# VentilatorRev1InterimDaughtercard.net
KiCad netlist of a schematic drawn in Altium Designer
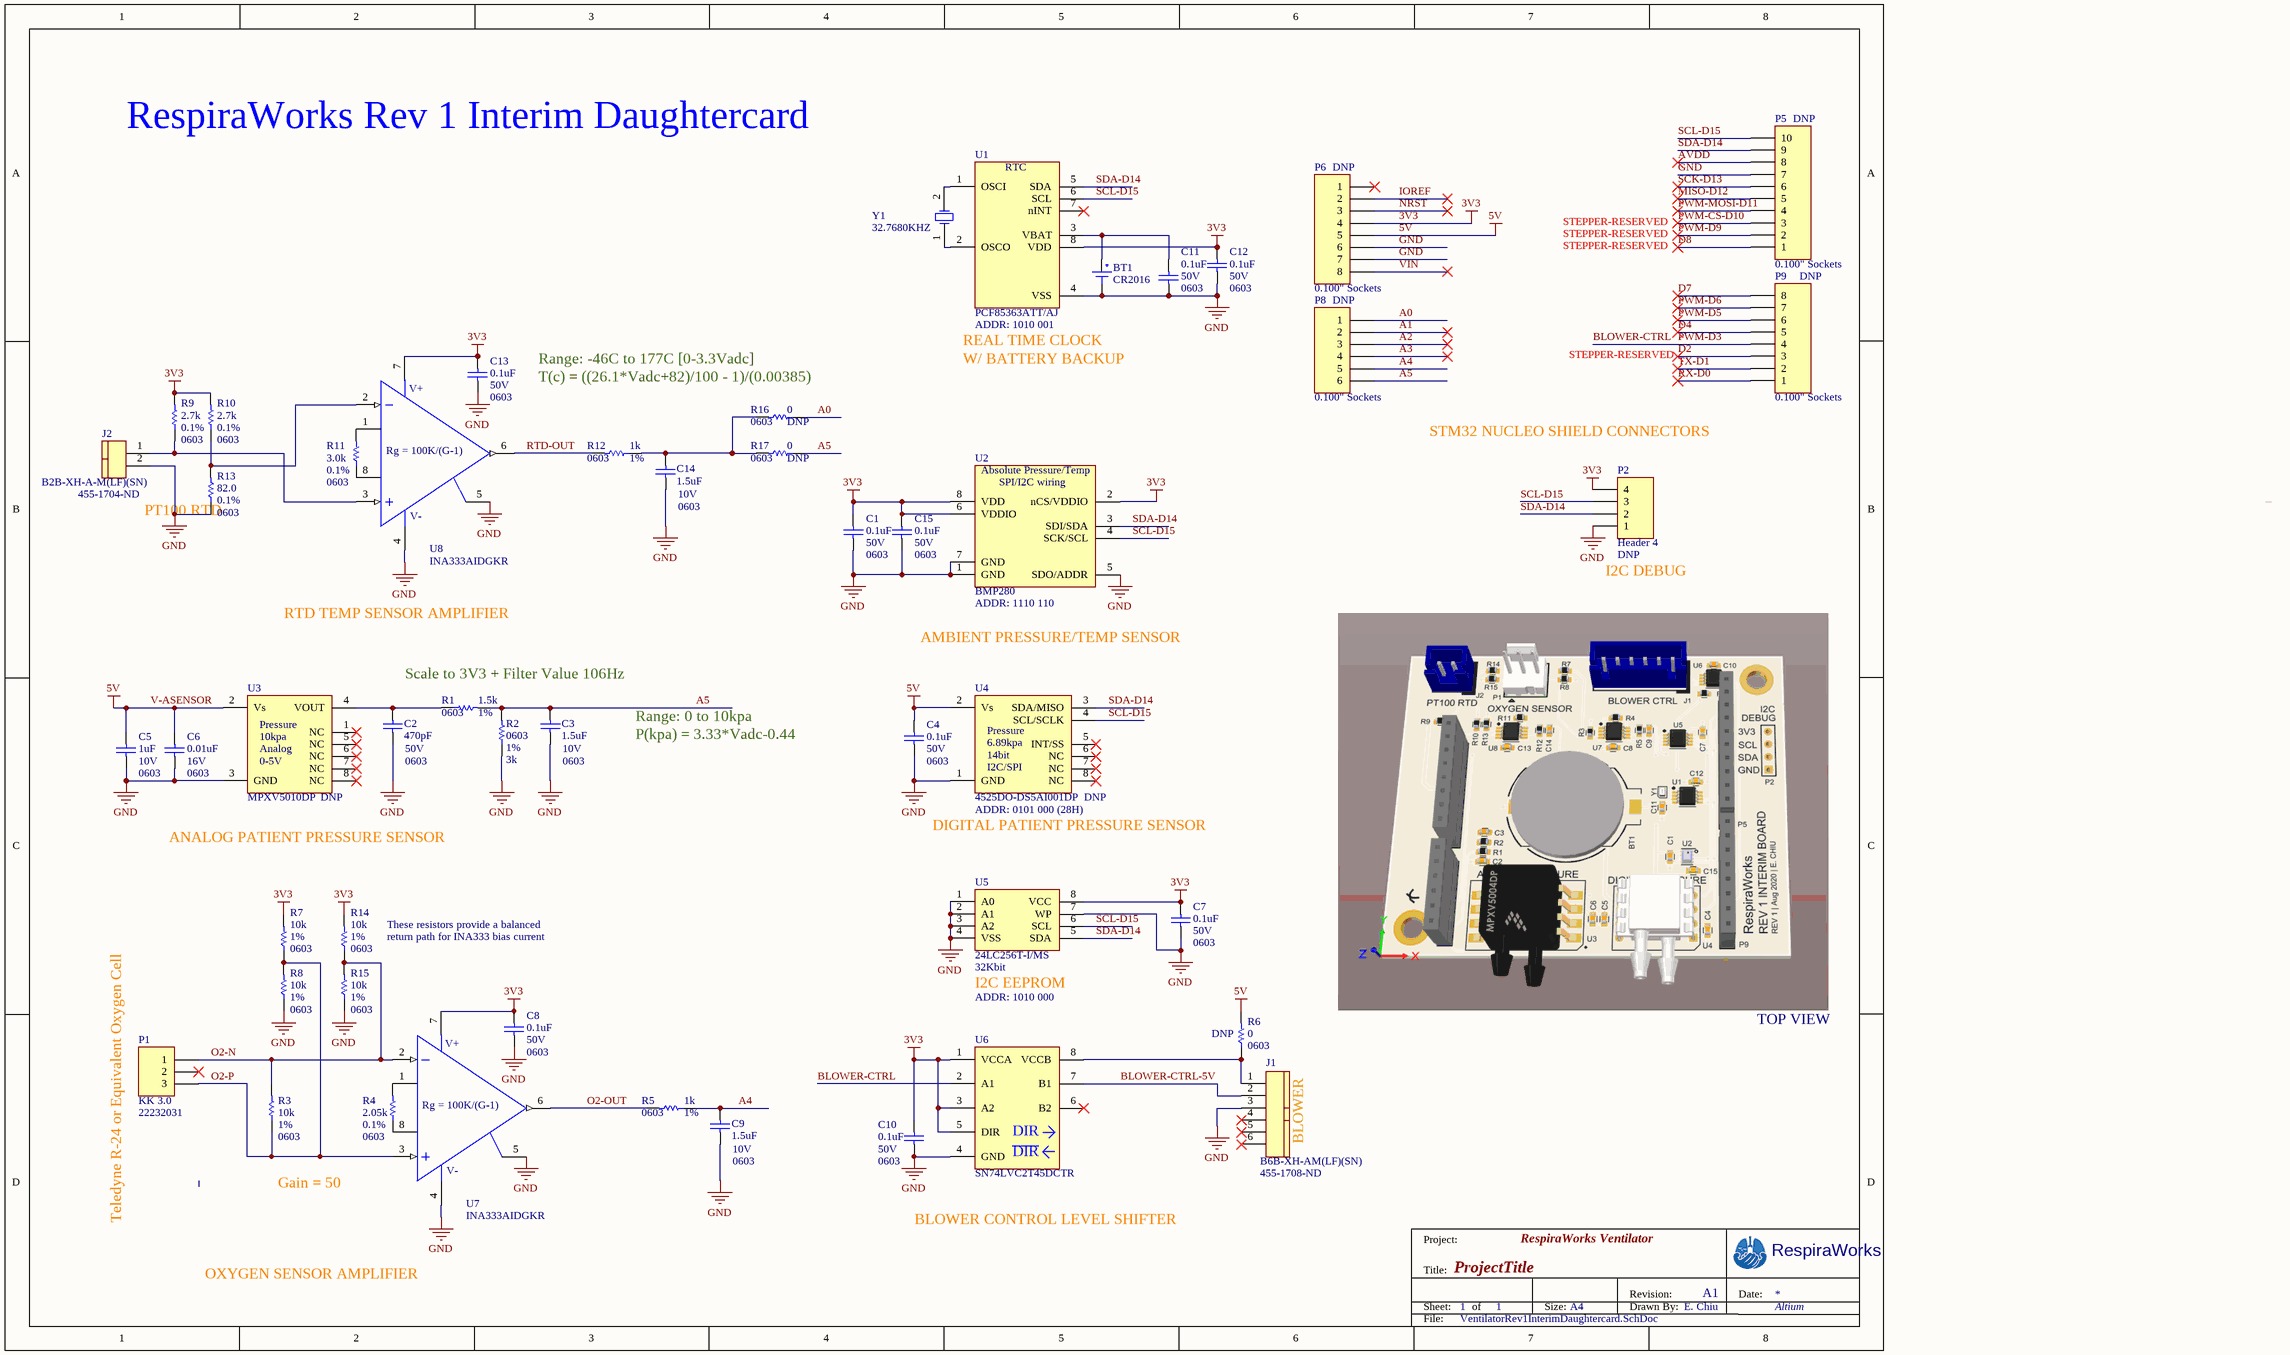
[diagram p0: VentilatorRev1InterimDaughtercard.SchDoc]

(export (version "E")
  (design (tool "Eeschema 10.0.6"))
  (components
    (comp (ref "BT1")
      (value "CR2016")
      (footprint "BLP20")
      (description "CR2016 Coil Cell Battery Holder")
      (fields (field (name "MANUFACTURER") "MPD") (field (name "VOLTAGE") "3V"))
      (libsource (lib "special") (part "BLP2016SM-GTR"))
    )
    (comp (ref "C1")
      (value "0.1uF")
      (footprint "CAP0603")
      (description "Cap 0603")
      (fields
        (field (name "MANUFACTURER") "Kemet")
        (field (name "VOLTAGE") "50V")
        (field (name "PCB PACKAGE") "0603")
        (field (name "Comment") "CAP 0603")
      )
      (libsource (lib "generic") (part "CAP 0603"))
    )
    (comp (ref "C2")
      (value "470pF")
      (footprint "CAP0603")
      (description "Cap 0603")
      (fields
        (field (name "MANUFACTURER") "Kemet")
        (field (name "VOLTAGE") "50V")
        (field (name "PCB PACKAGE") "0603")
        (field (name "Comment") "CAP 0603")
      )
      (libsource (lib "generic") (part "CAP 0603"))
    )
    (comp (ref "C3")
      (value "1.5uF")
      (footprint "CAP0603")
      (description "Cap 0603")
      (fields
        (field (name "MANUFACTURER") "TDK")
        (field (name "VOLTAGE") "10V")
        (field (name "PCB PACKAGE") "0603")
        (field (name "Comment") "CAP 0603")
      )
      (libsource (lib "generic") (part "CAP 0603"))
    )
    (comp (ref "C4")
      (value "0.1uF")
      (footprint "CAP0603")
      (description "Cap 0603")
      (fields
        (field (name "MANUFACTURER") "Kemet")
        (field (name "VOLTAGE") "50V")
        (field (name "PCB PACKAGE") "0603")
        (field (name "Comment") "CAP 0603")
      )
      (libsource (lib "generic") (part "CAP 0603"))
    )
    (comp (ref "C5")
      (value "1uF")
      (footprint "CAP0603")
      (description "Cap 0603")
      (fields
        (field (name "MANUFACTURER") "Yageo")
        (field (name "VOLTAGE") "10V")
        (field (name "PCB PACKAGE") "0603")
        (field (name "Comment") "CAP 0603")
      )
      (libsource (lib "generic") (part "CAP 0603"))
    )
    (comp (ref "C6")
      (value "0.01uF")
      (footprint "CAP0603")
      (description "Cap 0603")
      (fields
        (field (name "MANUFACTURER") "Samsung")
        (field (name "VOLTAGE") "16V")
        (field (name "PCB PACKAGE") "0603")
        (field (name "Comment") "CAP 0603")
      )
      (libsource (lib "generic") (part "CAP 0603"))
    )
    (comp (ref "C7")
      (value "0.1uF")
      (footprint "CAP0603")
      (description "Cap 0603")
      (fields
        (field (name "MANUFACTURER") "Kemet")
        (field (name "VOLTAGE") "50V")
        (field (name "PCB PACKAGE") "0603")
        (field (name "Comment") "CAP 0603")
      )
      (libsource (lib "generic") (part "CAP 0603"))
    )
    (comp (ref "C8")
      (value "0.1uF")
      (footprint "CAP0603")
      (description "Cap 0603")
      (fields
        (field (name "MANUFACTURER") "Kemet")
        (field (name "VOLTAGE") "50V")
        (field (name "PCB PACKAGE") "0603")
        (field (name "Comment") "CAP 0603")
      )
      (libsource (lib "generic") (part "CAP 0603"))
    )
    (comp (ref "C9")
      (value "1.5uF")
      (footprint "CAP0603")
      (description "Cap 0603")
      (fields
        (field (name "MANUFACTURER") "TDK")
        (field (name "VOLTAGE") "10V")
        (field (name "PCB PACKAGE") "0603")
        (field (name "Comment") "CAP 0603")
      )
      (libsource (lib "generic") (part "CAP 0603"))
    )
    (comp (ref "C10")
      (value "0.1uF")
      (footprint "CAP0603")
      (description "Cap 0603")
      (fields
        (field (name "MANUFACTURER") "Kemet")
        (field (name "VOLTAGE") "50V")
        (field (name "PCB PACKAGE") "0603")
        (field (name "Comment") "CAP 0603")
      )
      (libsource (lib "generic") (part "CAP 0603"))
    )
    (comp (ref "C11")
      (value "0.1uF")
      (footprint "CAP0603")
      (description "Cap 0603")
      (fields
        (field (name "MANUFACTURER") "Kemet")
        (field (name "VOLTAGE") "50V")
        (field (name "PCB PACKAGE") "0603")
        (field (name "Comment") "CAP 0603")
      )
      (libsource (lib "generic") (part "CAP 0603"))
    )
    (comp (ref "C12")
      (value "0.1uF")
      (footprint "CAP0603")
      (description "Cap 0603")
      (fields
        (field (name "MANUFACTURER") "Kemet")
        (field (name "VOLTAGE") "50V")
        (field (name "PCB PACKAGE") "0603")
        (field (name "Comment") "CAP 0603")
      )
      (libsource (lib "generic") (part "CAP 0603"))
    )
    (comp (ref "C13")
      (value "0.1uF")
      (footprint "CAP0603")
      (description "Cap 0603")
      (fields
        (field (name "MANUFACTURER") "Kemet")
        (field (name "VOLTAGE") "50V")
        (field (name "PCB PACKAGE") "0603")
        (field (name "Comment") "CAP 0603")
      )
      (libsource (lib "generic") (part "CAP 0603"))
    )
    (comp (ref "C14")
      (value "1.5uF")
      (footprint "CAP0603")
      (description "Cap 0603")
      (fields
        (field (name "MANUFACTURER") "TDK")
        (field (name "VOLTAGE") "10V")
        (field (name "PCB PACKAGE") "0603")
        (field (name "Comment") "CAP 0603")
      )
      (libsource (lib "generic") (part "CAP 0603"))
    )
    (comp (ref "C15")
      (value "0.1uF")
      (footprint "CAP0603")
      (description "Cap 0603")
      (fields
        (field (name "MANUFACTURER") "Kemet")
        (field (name "VOLTAGE") "50V")
        (field (name "PCB PACKAGE") "0603")
        (field (name "Comment") "CAP 0603")
      )
      (libsource (lib "generic") (part "CAP 0603"))
    )
    (comp (ref "J1")
      (value "B6B-XH-AM(LF)(SN)")
      (footprint "JST_B6B-XH-AM")
      (description "CONN HEADER VERT 6POS 2.5MM")
      (fields
        (field (name "MANUFACTURER") "JST Sales America Inc.")
        (field (name "MANUFACTURER P/N") "B6B-XH-AM(LF)(SN)")
        (field (name "SUPPLIER PART NUMBER 1") "455-1708-ND")
      )
      (libsource (lib "JST XH") (part "B6B-XH-AM(LF)(SN)"))
    )
    (comp (ref "J2")
      (value "B2B-XH-AM(LF)(SN)")
      (footprint "JST_B2B-XH-AM")
      (description "CONN HEADER VERT 2POS 2.5MM")
      (fields
        (field (name "MANUFACTURER") "JST Sales America Inc.")
        (field (name "MANUFACTURER P/N") "B2B-XH-A-M(LF)(SN)")
        (field (name "SUPPLIER PART NUMBER 1") "455-1704-ND")
      )
      (libsource (lib "JST XH") (part "B2B-XH-AM(LF)(SN)"))
    )
    (comp (ref "P1")
      (value "KK 3.0")
      (footprint "22232031")
      (description "Conn, KK 0.100\" Male Header")
      (fields (field (name "MANUFACTURER") "Molex") (field (name "MANUFACTURER P/N") "22232031"))
      (libsource (lib "molex") (part "22232031"))
    )
    (comp (ref "P2")
      (value "Header 4")
      (footprint "HDR1X4")
      (description "Header, 4-Pin")
      (fields (field (name "DO NOT POPULATE") "DNP") (field (name "PUBLISHER") "Altium Limited"))
      (libsource (lib "Miscellaneous Connectors") (part "Header 4"))
    )
    (comp (ref "P5")
      (value "0.100\" Sockets")
      (footprint "ESQ-110-14-T-S")
      (description "Tall Female Header 0.100\" Pitch 8x1 Sockets")
      (fields (field (name "MANUFACTURER") "Samtec") (field (name "DO NOT POPULATE") "DNP"))
      (libsource (lib "samtec") (part "ESQ-110-14-T-S"))
    )
    (comp (ref "P6")
      (value "0.100\" Sockets")
      (footprint "ESQ-108-14-T-S")
      (description "Tall Female Header 0.100\" Pitch 8x1 Sockets")
      (fields (field (name "MANUFACTURER") "Samtec") (field (name "DO NOT POPULATE") "DNP"))
      (libsource (lib "samtec") (part "ESQ-108-14-T-S"))
    )
    (comp (ref "P8")
      (value "0.100\" Sockets")
      (footprint "ESQ-106-14-T-S")
      (description "Tall Female Header 0.100\" Pitch 6x1 Sockets")
      (fields (field (name "MANUFACTURER") "Samtec") (field (name "DO NOT POPULATE") "DNP"))
      (libsource (lib "samtec") (part "ESQ-106-14-T-S"))
    )
    (comp (ref "P9")
      (value "0.100\" Sockets")
      (footprint "ESQ-108-14-T-S")
      (description "Tall Female Header 0.100\" Pitch 8x1 Sockets")
      (fields (field (name "MANUFACTURER") "Samtec") (field (name "DO NOT POPULATE") "DNP"))
      (libsource (lib "") (part "ESQ-108-14-T-S_1"))
    )
    (comp (ref "R1")
      (value "1.5k")
      (footprint "RES0603")
      (description "Res 0603")
      (fields
        (field (name "MANUFACTURER") "Yageo")
        (field (name "PCB PACKAGE") "0603")
        (field (name "TOLERANCE") "1%")
        (field (name "Comment") "RES 0603")
      )
      (libsource (lib "generic") (part "RES 0603"))
    )
    (comp (ref "R2")
      (value "3k")
      (footprint "RES0603")
      (description "Res 0603")
      (fields
        (field (name "MANUFACTURER") "Yageo")
        (field (name "PCB PACKAGE") "0603")
        (field (name "TOLERANCE") "1%")
        (field (name "Comment") "RES 0603")
      )
      (libsource (lib "generic") (part "RES 0603"))
    )
    (comp (ref "R3")
      (value "10k")
      (footprint "RES0603")
      (description "Res 0603")
      (fields
        (field (name "MANUFACTURER") "Yageo")
        (field (name "PCB PACKAGE") "0603")
        (field (name "TOLERANCE") "1%")
        (field (name "Comment") "RES 0603")
      )
      (libsource (lib "generic") (part "RES 0603"))
    )
    (comp (ref "R4")
      (value "2.05k")
      (footprint "RES0603")
      (description "Res 0603")
      (fields
        (field (name "MANUFACTURER") "Yageo")
        (field (name "PCB PACKAGE") "0603")
        (field (name "TOLERANCE") "0.1%")
        (field (name "Comment") "RES 0603")
      )
      (libsource (lib "generic") (part "RES 0603"))
    )
    (comp (ref "R5")
      (value "1k")
      (footprint "RES0603")
      (description "Res 0603")
      (fields
        (field (name "MANUFACTURER") "Yageo")
        (field (name "PCB PACKAGE") "0603")
        (field (name "TOLERANCE") "1%")
        (field (name "Comment") "RES 0603")
      )
      (libsource (lib "generic") (part "RES 0603"))
    )
    (comp (ref "R6")
      (value "0")
      (footprint "RES0603")
      (description "Res 0603")
      (fields
        (field (name "MANUFACTURER") "Yageo")
        (field (name "PCB PACKAGE") "0603")
        (field (name "TOLERANCE") "5%")
        (field (name "DO NOT POPULATE") "DNP")
      )
      (libsource (lib "generic") (part "RES 0603"))
    )
    (comp (ref "R7")
      (value "10k")
      (footprint "RES0603")
      (description "Res 0603")
      (fields
        (field (name "MANUFACTURER") "Yageo")
        (field (name "PCB PACKAGE") "0603")
        (field (name "TOLERANCE") "1%")
        (field (name "Comment") "RES 0603")
      )
      (libsource (lib "generic") (part "RES 0603"))
    )
    (comp (ref "R8")
      (value "10k")
      (footprint "RES0603")
      (description "Res 0603")
      (fields
        (field (name "MANUFACTURER") "Yageo")
        (field (name "PCB PACKAGE") "0603")
        (field (name "TOLERANCE") "1%")
        (field (name "Comment") "RES 0603")
      )
      (libsource (lib "generic") (part "RES 0603"))
    )
    (comp (ref "R9")
      (value "2.7k")
      (footprint "RES0603")
      (description "Res 0603")
      (fields
        (field (name "MANUFACTURER") "Panasonic")
        (field (name "PCB PACKAGE") "0603")
        (field (name "TOLERANCE") "0.1%")
        (field (name "Comment") "RES 0603")
      )
      (libsource (lib "generic") (part "RES 0603"))
    )
    (comp (ref "R10")
      (value "2.7k")
      (footprint "RES0603")
      (description "Res 0603")
      (fields
        (field (name "MANUFACTURER") "Panasonic")
        (field (name "PCB PACKAGE") "0603")
        (field (name "TOLERANCE") "0.1%")
        (field (name "Comment") "RES 0603")
      )
      (libsource (lib "generic") (part "RES 0603"))
    )
    (comp (ref "R11")
      (value "3.0k")
      (footprint "RES0603")
      (description "Res 0603")
      (fields
        (field (name "MANUFACTURER") "Yageo")
        (field (name "PCB PACKAGE") "0603")
        (field (name "TOLERANCE") "0.1%")
        (field (name "Comment") "RES 0603")
      )
      (libsource (lib "generic") (part "RES 0603"))
    )
    (comp (ref "R12")
      (value "1k")
      (footprint "RES0603")
      (description "Res 0603")
      (fields
        (field (name "MANUFACTURER") "Yageo")
        (field (name "PCB PACKAGE") "0603")
        (field (name "TOLERANCE") "1%")
        (field (name "Comment") "RES 0603")
      )
      (libsource (lib "generic") (part "RES 0603"))
    )
    (comp (ref "R13")
      (value "82.0")
      (footprint "RES0603")
      (description "Res 0603")
      (fields
        (field (name "MANUFACTURER") "Panasonic")
        (field (name "PCB PACKAGE") "0603")
        (field (name "TOLERANCE") "0.1%")
        (field (name "Comment") "RES 0603")
      )
      (libsource (lib "generic") (part "RES 0603"))
    )
    (comp (ref "R14")
      (value "10k")
      (footprint "RES0603")
      (description "Res 0603")
      (fields
        (field (name "MANUFACTURER") "Yageo")
        (field (name "PCB PACKAGE") "0603")
        (field (name "TOLERANCE") "1%")
        (field (name "Comment") "RES 0603")
      )
      (libsource (lib "generic") (part "RES 0603"))
    )
    (comp (ref "R15")
      (value "10k")
      (footprint "RES0603")
      (description "Res 0603")
      (fields
        (field (name "MANUFACTURER") "Yageo")
        (field (name "PCB PACKAGE") "0603")
        (field (name "TOLERANCE") "1%")
        (field (name "Comment") "RES 0603")
      )
      (libsource (lib "generic") (part "RES 0603"))
    )
    (comp (ref "R16")
      (value "0")
      (footprint "RES0603")
      (description "Res 0603")
      (fields
        (field (name "MANUFACTURER") "Yageo")
        (field (name "PCB PACKAGE") "0603")
        (field (name "TOLERANCE") "5%")
        (field (name "DO NOT POPULATE") "DNP")
      )
      (libsource (lib "generic") (part "RES 0603"))
    )
    (comp (ref "R17")
      (value "0")
      (footprint "RES0603")
      (description "Res 0603")
      (fields
        (field (name "MANUFACTURER") "Yageo")
        (field (name "PCB PACKAGE") "0603")
        (field (name "TOLERANCE") "5%")
        (field (name "DO NOT POPULATE") "DNP")
      )
      (libsource (lib "generic") (part "RES 0603"))
    )
    (comp (ref "U1")
      (value "PCF85363ATT/AJ")
      (footprint "8-MSOP-3.0MM")
      (fields (field (name "MANUFACTURER") "NXP") (field (name "MANUFACTURER P/N") "PCF85363ATT/AJ"))
      (libsource (lib "nxp") (part "PCF85363ATT/AJ"))
    )
    (comp (ref "U2")
      (value "BMP280")
      (footprint "BMP280")
      (description "Pressure Sensor 4.35PSI ~ 15.95PSI (30kPa ~ 110kPa) Absolute  16b 8-SMD")
      (fields (field (name "MANUFACTURER") "Bosch Sensortec") (field (name "MANUFACTURER P/N") "BMP280"))
      (libsource (lib "special") (part "BMP280"))
    )
    (comp (ref "U3")
      (value "MPXV5010DP")
      (footprint "8-SOP-MPXV")
      (fields
        (field (name "DO NOT POPULATE") "DNP")
        (field (name "MANUFACTURER") "NXP")
        (field (name "MANUFACTURER P/N") "MPXV5010DP")
      )
      (libsource (lib "nxp") (part "MPXV5010DP"))
    )
    (comp (ref "U4")
      (value "4525DO-DS5AI001DP")
      (footprint "4525do")
      (description "Pressure Sensor 1PSI (6.89kPa) Differential Male - 0.14\" (3.56mm) Tube, Dual 14 b 8-DIP Module")
      (fields
        (field (name "DO NOT POPULATE") "DNP")
        (field (name "MANUFACTURER") "TE Connectivity")
        (field (name "MANUFACTURER P/N") "4525DO-DS5AI001DP")
      )
      (libsource (lib "te_connectivity") (part "4525DO-DS5AI001DP"))
    )
    (comp (ref "U5")
      (value "32Kbit")
      (footprint "8-MSOP")
      (description "IC EEPROM 256KBIT I2C 400KHZ 8MSOP")
      (fields
        (field (name "MANUFACTURER") "Microchip")
        (field (name "TOLERANCE") "25ppm")
        (field (name "MANUFACTURER P/N") "24LC256T-I/MS")
      )
      (libsource (lib "microchip") (part "24LC256T-I/MS"))
    )
    (comp (ref "U6")
      (value "SN74LVC2T45DCTR")
      (footprint "8-MSOP")
      (description "Bidirectional Level Shifter 2-ch")
      (fields
        (field (name "MANUFACTURER") "Texas Instruments")
        (field (name "MANUFACTURER P/N") "SN74LVC2T45DCTR")
      )
      (libsource (lib "ti") (part "SN74LVC2T45DCTR"))
    )
    (comp (ref "U7")
      (value "INA333")
      (footprint "8-VSSOP")
      (description "Instrumentation Amp, GBW=1MHz")
      (fields
        (field (name "MANUFACTURER") "Texas Instruments")
        (field (name "MANUFACTURER P/N") "INA333AIDGKR")
      )
      (libsource (lib "ti") (part "INA333"))
    )
    (comp (ref "U8")
      (value "INA333")
      (footprint "8-VSSOP")
      (description "Instrumentation Amp, GBW=1MHz")
      (fields
        (field (name "MANUFACTURER") "Texas Instruments")
        (field (name "MANUFACTURER P/N") "INA333AIDGKR")
      )
      (libsource (lib "ti") (part "INA333"))
    )
    (comp (ref "Y1")
      (value "32.7680KHZ")
      (footprint "2-ABS05")
      (description "CRYSTAL 32.7680KHZ 12.5PF SMD 1x1.6mm")
      (fields (field (name "MANUFACTURER") "Abracon") (field (name "TOLERANCE") "20ppm"))
      (libsource (lib "abracon") (part "ABS05-32.768KHZ-T"))
    )
  )
  (nets
    (net (code "1") (name "/A0") (class "Default")
      (node (ref "P8") (pin "1") (pinfunction "1_1") (pintype "passive"))
      (node (ref "R16") (pin "1") (pinfunction "1_1") (pintype "passive"))
    )
    (net (code "2") (name "/A1") (class "Default")
      (node (ref "P8") (pin "2") (pinfunction "2_2") (pintype "passive+no_connect"))
    )
    (net (code "3") (name "/A2") (class "Default")
      (node (ref "P8") (pin "3") (pinfunction "3_3") (pintype "passive+no_connect"))
    )
    (net (code "4") (name "/A3") (class "Default")
      (node (ref "P8") (pin "4") (pinfunction "4_4") (pintype "passive+no_connect"))
    )
    (net (code "5") (name "/A4") (class "Default")
      (node (ref "C9") (pin "2") (pinfunction "2_2") (pintype "passive"))
      (node (ref "P8") (pin "5") (pinfunction "5_5") (pintype "passive"))
      (node (ref "R5") (pin "1") (pinfunction "1_1") (pintype "passive"))
    )
    (net (code "6") (name "/A5") (class "Default")
      (node (ref "C3") (pin "2") (pinfunction "2_2") (pintype "passive"))
      (node (ref "P8") (pin "6") (pinfunction "6_6") (pintype "passive"))
      (node (ref "R1") (pin "2") (pinfunction "2_2") (pintype "passive"))
      (node (ref "R17") (pin "1") (pinfunction "1_1") (pintype "passive"))
      (node (ref "R2") (pin "2") (pinfunction "2_2") (pintype "passive"))
    )
    (net (code "7") (name "/AVDD") (class "Default")
      (node (ref "P5") (pin "8") (pinfunction "8_8") (pintype "passive+no_connect"))
    )
    (net (code "8") (name "/BLOWER-CTRL") (class "Default")
      (node (ref "P9") (pin "4") (pinfunction "4_4") (pintype "passive"))
      (node (ref "U6") (pin "2") (pinfunction "A1_2") (pintype "passive"))
    )
    (net (code "9") (name "/BLOWER-CTRL-5V") (class "Default")
      (node (ref "J1") (pin "2") (pinfunction "2_2") (pintype "passive"))
      (node (ref "U6") (pin "7") (pinfunction "B1_7") (pintype "passive"))
    )
    (net (code "10") (name "/D2") (class "Default")
      (node (ref "P9") (pin "3") (pinfunction "3_3") (pintype "passive+no_connect"))
    )
    (net (code "11") (name "/D4") (class "Default")
      (node (ref "P9") (pin "5") (pinfunction "5_5") (pintype "passive+no_connect"))
    )
    (net (code "12") (name "/D7") (class "Default")
      (node (ref "P9") (pin "8") (pinfunction "8_8") (pintype "passive+no_connect"))
    )
    (net (code "13") (name "/D8") (class "Default")
      (node (ref "P5") (pin "1") (pinfunction "1_1") (pintype "passive+no_connect"))
    )
    (net (code "14") (name "/IOREF") (class "Default")
      (node (ref "P6") (pin "2") (pinfunction "2_2") (pintype "passive+no_connect"))
    )
    (net (code "15") (name "/MISO-D12") (class "Default")
      (node (ref "P5") (pin "5") (pinfunction "5_5") (pintype "passive+no_connect"))
    )
    (net (code "16") (name "/NRST") (class "Default")
      (node (ref "P6") (pin "3") (pinfunction "3_3") (pintype "passive+no_connect"))
    )
    (net (code "17") (name "/O2-N") (class "Default")
      (node (ref "P1") (pin "1") (pinfunction "1_1") (pintype "passive"))
      (node (ref "R14") (pin "1") (pinfunction "1_1") (pintype "passive"))
      (node (ref "R15") (pin "2") (pinfunction "2_2") (pintype "passive"))
      (node (ref "R3") (pin "2") (pinfunction "2_2") (pintype "passive"))
      (node (ref "U7") (pin "2") (pinfunction "IN-_2") (pintype "input"))
    )
    (net (code "18") (name "/O2-OUT") (class "Default")
      (node (ref "R5") (pin "2") (pinfunction "2_2") (pintype "passive"))
      (node (ref "U7") (pin "6") (pinfunction "OUT_6") (pintype "output"))
    )
    (net (code "19") (name "/O2-P") (class "Default")
      (node (ref "P1") (pin "3") (pinfunction "3_3") (pintype "passive"))
      (node (ref "R3") (pin "1") (pinfunction "1_1") (pintype "passive"))
      (node (ref "R7") (pin "1") (pinfunction "1_1") (pintype "passive"))
      (node (ref "R8") (pin "2") (pinfunction "2_2") (pintype "passive"))
      (node (ref "U7") (pin "3") (pinfunction "IN+_3") (pintype "input"))
    )
    (net (code "20") (name "/PWM-CS-D10") (class "Default")
      (node (ref "P5") (pin "3") (pinfunction "3_3") (pintype "passive+no_connect"))
    )
    (net (code "21") (name "/PWM-D5") (class "Default")
      (node (ref "P9") (pin "6") (pinfunction "6_6") (pintype "passive+no_connect"))
    )
    (net (code "22") (name "/PWM-D6") (class "Default")
      (node (ref "P9") (pin "7") (pinfunction "7_7") (pintype "passive+no_connect"))
    )
    (net (code "23") (name "/PWM-D9") (class "Default")
      (node (ref "P5") (pin "2") (pinfunction "2_2") (pintype "passive+no_connect"))
    )
    (net (code "24") (name "/PWM-MOSI-D11") (class "Default")
      (node (ref "P5") (pin "4") (pinfunction "4_4") (pintype "passive+no_connect"))
    )
    (net (code "25") (name "/RTD-OUT") (class "Default")
      (node (ref "R12") (pin "2") (pinfunction "2_2") (pintype "passive"))
      (node (ref "U8") (pin "6") (pinfunction "OUT_6") (pintype "output"))
    )
    (net (code "26") (name "/RX-D0") (class "Default")
      (node (ref "P9") (pin "1") (pinfunction "1_1") (pintype "passive+no_connect"))
    )
    (net (code "27") (name "/SCK-D13") (class "Default")
      (node (ref "P5") (pin "6") (pinfunction "6_6") (pintype "passive+no_connect"))
    )
    (net (code "28") (name "/SCL-D15") (class "Default")
      (node (ref "P2") (pin "3") (pinfunction "3_3") (pintype "passive"))
      (node (ref "P5") (pin "10") (pinfunction "10_10") (pintype "passive"))
      (node (ref "U1") (pin "6") (pinfunction "SCL_6") (pintype "passive"))
      (node (ref "U2") (pin "4") (pinfunction "SCK/SCL_4") (pintype "passive"))
      (node (ref "U4") (pin "4") (pinfunction "SCL/SCLK_4") (pintype "passive"))
      (node (ref "U5") (pin "6") (pinfunction "SCL_6") (pintype "passive"))
    )
    (net (code "29") (name "/SDA-D14") (class "Default")
      (node (ref "P2") (pin "2") (pinfunction "2_2") (pintype "passive"))
      (node (ref "P5") (pin "9") (pinfunction "9_9") (pintype "passive"))
      (node (ref "U1") (pin "5") (pinfunction "SDA_5") (pintype "passive"))
      (node (ref "U2") (pin "3") (pinfunction "SDI/SDA_3") (pintype "passive"))
      (node (ref "U4") (pin "3") (pinfunction "SDA/MISO_3") (pintype "passive"))
      (node (ref "U5") (pin "5") (pinfunction "SDA_5") (pintype "passive"))
    )
    (net (code "30") (name "/TX-D1") (class "Default")
      (node (ref "P9") (pin "2") (pinfunction "2_2") (pintype "passive+no_connect"))
    )
    (net (code "31") (name "/VIN") (class "Default")
      (node (ref "P6") (pin "8") (pinfunction "8_8") (pintype "passive+no_connect"))
    )
    (net (code "32") (name "3V3") (class "Default")
      (node (ref "C1") (pin "2") (pinfunction "2_2") (pintype "passive"))
      (node (ref "C10") (pin "2") (pinfunction "2_2") (pintype "passive"))
      (node (ref "C12") (pin "2") (pinfunction "2_2") (pintype "passive"))
      (node (ref "C13") (pin "2") (pinfunction "2_2") (pintype "passive"))
      (node (ref "C15") (pin "2") (pinfunction "2_2") (pintype "passive"))
      (node (ref "C7") (pin "2") (pinfunction "2_2") (pintype "passive"))
      (node (ref "C8") (pin "2") (pinfunction "2_2") (pintype "passive"))
      (node (ref "P2") (pin "4") (pinfunction "4_4") (pintype "passive"))
      (node (ref "P6") (pin "4") (pinfunction "4_4") (pintype "passive"))
      (node (ref "R10") (pin "2") (pinfunction "2_2") (pintype "passive"))
      (node (ref "R14") (pin "2") (pinfunction "2_2") (pintype "passive"))
      (node (ref "R7") (pin "2") (pinfunction "2_2") (pintype "passive"))
      (node (ref "R9") (pin "2") (pinfunction "2_2") (pintype "passive"))
      (node (ref "U1") (pin "8") (pinfunction "VDD_8") (pintype "passive"))
      (node (ref "U2") (pin "2") (pinfunction "nCS/VDDIO_2") (pintype "passive"))
      (node (ref "U2") (pin "6") (pinfunction "VDDIO_6") (pintype "passive"))
      (node (ref "U2") (pin "8") (pinfunction "VDD_8") (pintype "passive"))
      (node (ref "U5") (pin "8") (pinfunction "VCC_8") (pintype "passive"))
      (node (ref "U6") (pin "1") (pinfunction "VCCA_1") (pintype "passive"))
      (node (ref "U6") (pin "3") (pinfunction "A2_3") (pintype "passive"))
      (node (ref "U6") (pin "5") (pinfunction "DIR_5") (pintype "passive"))
      (node (ref "U7") (pin "7") (pinfunction "V+_7") (pintype "power_in"))
      (node (ref "U8") (pin "7") (pinfunction "V+_7") (pintype "power_in"))
    )
    (net (code "33") (name "5V") (class "Default")
      (node (ref "C4") (pin "2") (pinfunction "2_2") (pintype "passive"))
      (node (ref "C5") (pin "1") (pinfunction "1_1") (pintype "passive"))
      (node (ref "C6") (pin "1") (pinfunction "1_1") (pintype "passive"))
      (node (ref "P6") (pin "5") (pinfunction "5_5") (pintype "passive"))
      (node (ref "R6") (pin "2") (pinfunction "2_2") (pintype "passive"))
      (node (ref "U3") (pin "2") (pinfunction "Vs_2") (pintype "passive"))
      (node (ref "U4") (pin "2") (pinfunction "Vs_2") (pintype "passive"))
    )
    (net (code "34") (name "GND") (class "Default")
      (node (ref "BT1") (pin "M") (pinfunction "M_M") (pintype "passive"))
      (node (ref "C1") (pin "1") (pinfunction "1_1") (pintype "passive"))
      (node (ref "C10") (pin "1") (pinfunction "1_1") (pintype "passive"))
      (node (ref "C11") (pin "1") (pinfunction "1_1") (pintype "passive"))
      (node (ref "C12") (pin "1") (pinfunction "1_1") (pintype "passive"))
      (node (ref "C13") (pin "1") (pinfunction "1_1") (pintype "passive"))
      (node (ref "C14") (pin "1") (pinfunction "1_1") (pintype "passive"))
      (node (ref "C15") (pin "1") (pinfunction "1_1") (pintype "passive"))
      (node (ref "C2") (pin "1") (pinfunction "1_1") (pintype "passive"))
      (node (ref "C3") (pin "1") (pinfunction "1_1") (pintype "passive"))
      (node (ref "C4") (pin "1") (pinfunction "1_1") (pintype "passive"))
      (node (ref "C5") (pin "2") (pinfunction "2_2") (pintype "passive"))
      (node (ref "C6") (pin "2") (pinfunction "2_2") (pintype "passive"))
      (node (ref "C7") (pin "1") (pinfunction "1_1") (pintype "passive"))
      (node (ref "C8") (pin "1") (pinfunction "1_1") (pintype "passive"))
      (node (ref "C9") (pin "1") (pinfunction "1_1") (pintype "passive"))
      (node (ref "J1") (pin "3") (pinfunction "3_3") (pintype "passive"))
      (node (ref "J2") (pin "2") (pinfunction "2_2") (pintype "passive"))
      (node (ref "P2") (pin "1") (pinfunction "1_1") (pintype "passive"))
      (node (ref "P5") (pin "7") (pinfunction "7_7") (pintype "passive"))
      (node (ref "P6") (pin "6") (pinfunction "6_6") (pintype "passive"))
      (node (ref "P6") (pin "7") (pinfunction "7_7") (pintype "passive"))
      (node (ref "R13") (pin "1") (pinfunction "1_1") (pintype "passive"))
      (node (ref "R15") (pin "1") (pinfunction "1_1") (pintype "passive"))
      (node (ref "R2") (pin "1") (pinfunction "1_1") (pintype "passive"))
      (node (ref "R8") (pin "1") (pinfunction "1_1") (pintype "passive"))
      (node (ref "U1") (pin "4") (pinfunction "VSS_4") (pintype "passive"))
      (node (ref "U2") (pin "1") (pinfunction "GND_1") (pintype "passive"))
      (node (ref "U2") (pin "5") (pinfunction "SDO/ADDR_5") (pintype "passive"))
      (node (ref "U2") (pin "7") (pinfunction "GND_7") (pintype "passive"))
      (node (ref "U3") (pin "3") (pinfunction "GND_3") (pintype "passive"))
      (node (ref "U4") (pin "1") (pinfunction "GND_1") (pintype "passive"))
      (node (ref "U5") (pin "1") (pinfunction "A0_1") (pintype "passive"))
      (node (ref "U5") (pin "2") (pinfunction "A1_2") (pintype "passive"))
      (node (ref "U5") (pin "3") (pinfunction "A2_3") (pintype "passive"))
      (node (ref "U5") (pin "4") (pinfunction "VSS_4") (pintype "passive"))
      (node (ref "U5") (pin "7") (pinfunction "WP_7") (pintype "passive"))
      (node (ref "U6") (pin "4") (pinfunction "GND_4") (pintype "passive"))
      (node (ref "U7") (pin "4") (pinfunction "V-_4") (pintype "power_in"))
      (node (ref "U7") (pin "5") (pinfunction "5_5") (pintype "passive"))
      (node (ref "U8") (pin "4") (pinfunction "V-_4") (pintype "power_in"))
      (node (ref "U8") (pin "5") (pinfunction "5_5") (pintype "passive"))
    )
    (net (code "35") (name "Net-(C14-Pad2)") (class "Default")
      (node (ref "C14") (pin "2") (pinfunction "2_2") (pintype "passive"))
      (node (ref "R12") (pin "1") (pinfunction "1_1") (pintype "passive"))
      (node (ref "R16") (pin "2") (pinfunction "2_2") (pintype "passive"))
      (node (ref "R17") (pin "2") (pinfunction "2_2") (pintype "passive"))
    )
    (net (code "36") (name "Net-(R4-Pad1)") (class "Default")
      (node (ref "R4") (pin "1") (pinfunction "1_1") (pintype "passive"))
      (node (ref "U7") (pin "8") (pinfunction "8_8") (pintype "passive"))
    )
    (net (code "37") (name "Net-(R4-Pad2)") (class "Default")
      (node (ref "R4") (pin "2") (pinfunction "2_2") (pintype "passive"))
      (node (ref "U7") (pin "1") (pinfunction "1_1") (pintype "passive"))
    )
    (net (code "38") (name "Net-(R11-Pad1)") (class "Default")
      (node (ref "R11") (pin "1") (pinfunction "1_1") (pintype "passive"))
      (node (ref "U8") (pin "8") (pinfunction "8_8") (pintype "passive"))
    )
    (net (code "39") (name "Net-(R11-Pad2)") (class "Default")
      (node (ref "R11") (pin "2") (pinfunction "2_2") (pintype "passive"))
      (node (ref "U8") (pin "1") (pinfunction "1_1") (pintype "passive"))
    )
    (net (code "40") (name "Net-(U1-OSCI)") (class "Default")
      (node (ref "U1") (pin "1") (pinfunction "OSCI_1") (pintype "passive"))
      (node (ref "Y1") (pin "2") (pinfunction "OSC2_2") (pintype "passive"))
    )
    (net (code "41") (name "Net-(U1-OSCO)") (class "Default")
      (node (ref "U1") (pin "2") (pinfunction "OSCO_2") (pintype "passive"))
      (node (ref "Y1") (pin "1") (pinfunction "OSC1_1") (pintype "passive"))
    )
    (net (code "42") (name "Net-(U1-VBAT)") (class "Default")
      (node (ref "BT1") (pin "P") (pinfunction "P_P") (pintype "passive"))
      (node (ref "C11") (pin "2") (pinfunction "2_2") (pintype "passive"))
      (node (ref "U1") (pin "3") (pinfunction "VBAT_3") (pintype "passive"))
    )
    (net (code "43") (name "Net-(U3-VOUT)") (class "Default")
      (node (ref "C2") (pin "2") (pinfunction "2_2") (pintype "passive"))
      (node (ref "R1") (pin "1") (pinfunction "1_1") (pintype "passive"))
      (node (ref "U3") (pin "4") (pinfunction "VOUT_4") (pintype "passive"))
    )
    (net (code "44") (name "Net-(U6-VCCB)") (class "Default")
      (node (ref "J1") (pin "1") (pinfunction "1_1") (pintype "passive"))
      (node (ref "R6") (pin "1") (pinfunction "1_1") (pintype "passive"))
      (node (ref "U6") (pin "8") (pinfunction "VCCB_8") (pintype "passive"))
    )
    (net (code "45") (name "Net-(U8-IN+)") (class "Default")
      (node (ref "J2") (pin "1") (pinfunction "1_1") (pintype "passive"))
      (node (ref "R9") (pin "1") (pinfunction "1_1") (pintype "passive"))
      (node (ref "U8") (pin "3") (pinfunction "IN+_3") (pintype "input"))
    )
    (net (code "46") (name "Net-(U8-IN-)") (class "Default")
      (node (ref "R10") (pin "1") (pinfunction "1_1") (pintype "passive"))
      (node (ref "R13") (pin "2") (pinfunction "2_2") (pintype "passive"))
      (node (ref "U8") (pin "2") (pinfunction "IN-_2") (pintype "input"))
    )
    (net (code "47") (name "unconnected-(J1-Pad4)") (class "Default")
      (node (ref "J1") (pin "4") (pinfunction "4_4") (pintype "passive+no_connect"))
    )
    (net (code "48") (name "unconnected-(J1-Pad5)") (class "Default")
      (node (ref "J1") (pin "5") (pinfunction "5_5") (pintype "passive+no_connect"))
    )
    (net (code "49") (name "unconnected-(J1-Pad6)") (class "Default")
      (node (ref "J1") (pin "6") (pinfunction "6_6") (pintype "passive+no_connect"))
    )
    (net (code "50") (name "unconnected-(P1-Pad2)") (class "Default")
      (node (ref "P1") (pin "2") (pinfunction "2_2") (pintype "passive+no_connect"))
    )
    (net (code "51") (name "unconnected-(P6-Pad1)") (class "Default")
      (node (ref "P6") (pin "1") (pinfunction "1_1") (pintype "passive+no_connect"))
    )
    (net (code "52") (name "unconnected-(U1-nINT-Pad7)") (class "Default")
      (node (ref "U1") (pin "7") (pinfunction "nINT_7") (pintype "passive+no_connect"))
    )
    (net (code "53") (name "unconnected-(U3-NC-Pad1)") (class "Default")
      (node (ref "U3") (pin "1") (pinfunction "NC_1") (pintype "passive+no_connect"))
    )
    (net (code "54") (name "unconnected-(U3-NC-Pad5)") (class "Default")
      (node (ref "U3") (pin "5") (pinfunction "NC_5") (pintype "passive+no_connect"))
    )
    (net (code "55") (name "unconnected-(U3-NC-Pad6)") (class "Default")
      (node (ref "U3") (pin "6") (pinfunction "NC_6") (pintype "passive+no_connect"))
    )
    (net (code "56") (name "unconnected-(U3-NC-Pad7)") (class "Default")
      (node (ref "U3") (pin "7") (pinfunction "NC_7") (pintype "passive+no_connect"))
    )
    (net (code "57") (name "unconnected-(U3-NC-Pad8)") (class "Default")
      (node (ref "U3") (pin "8") (pinfunction "NC_8") (pintype "passive+no_connect"))
    )
    (net (code "58") (name "unconnected-(U4-INT{slash}SS-Pad5)") (class "Default")
      (node (ref "U4") (pin "5") (pinfunction "INT/SS_5") (pintype "passive+no_connect"))
    )
    (net (code "59") (name "unconnected-(U4-NC-Pad6)") (class "Default")
      (node (ref "U4") (pin "6") (pinfunction "NC_6") (pintype "passive+no_connect"))
    )
    (net (code "60") (name "unconnected-(U4-NC-Pad7)") (class "Default")
      (node (ref "U4") (pin "7") (pinfunction "NC_7") (pintype "passive+no_connect"))
    )
    (net (code "61") (name "unconnected-(U4-NC-Pad8)") (class "Default")
      (node (ref "U4") (pin "8") (pinfunction "NC_8") (pintype "passive+no_connect"))
    )
    (net (code "62") (name "unconnected-(U6-B2-Pad6)") (class "Default")
      (node (ref "U6") (pin "6") (pinfunction "B2_6") (pintype "passive+no_connect"))
    )
  )
)
